# kijek.net
KiCad netlist of a schematic drawn in Altium Designer
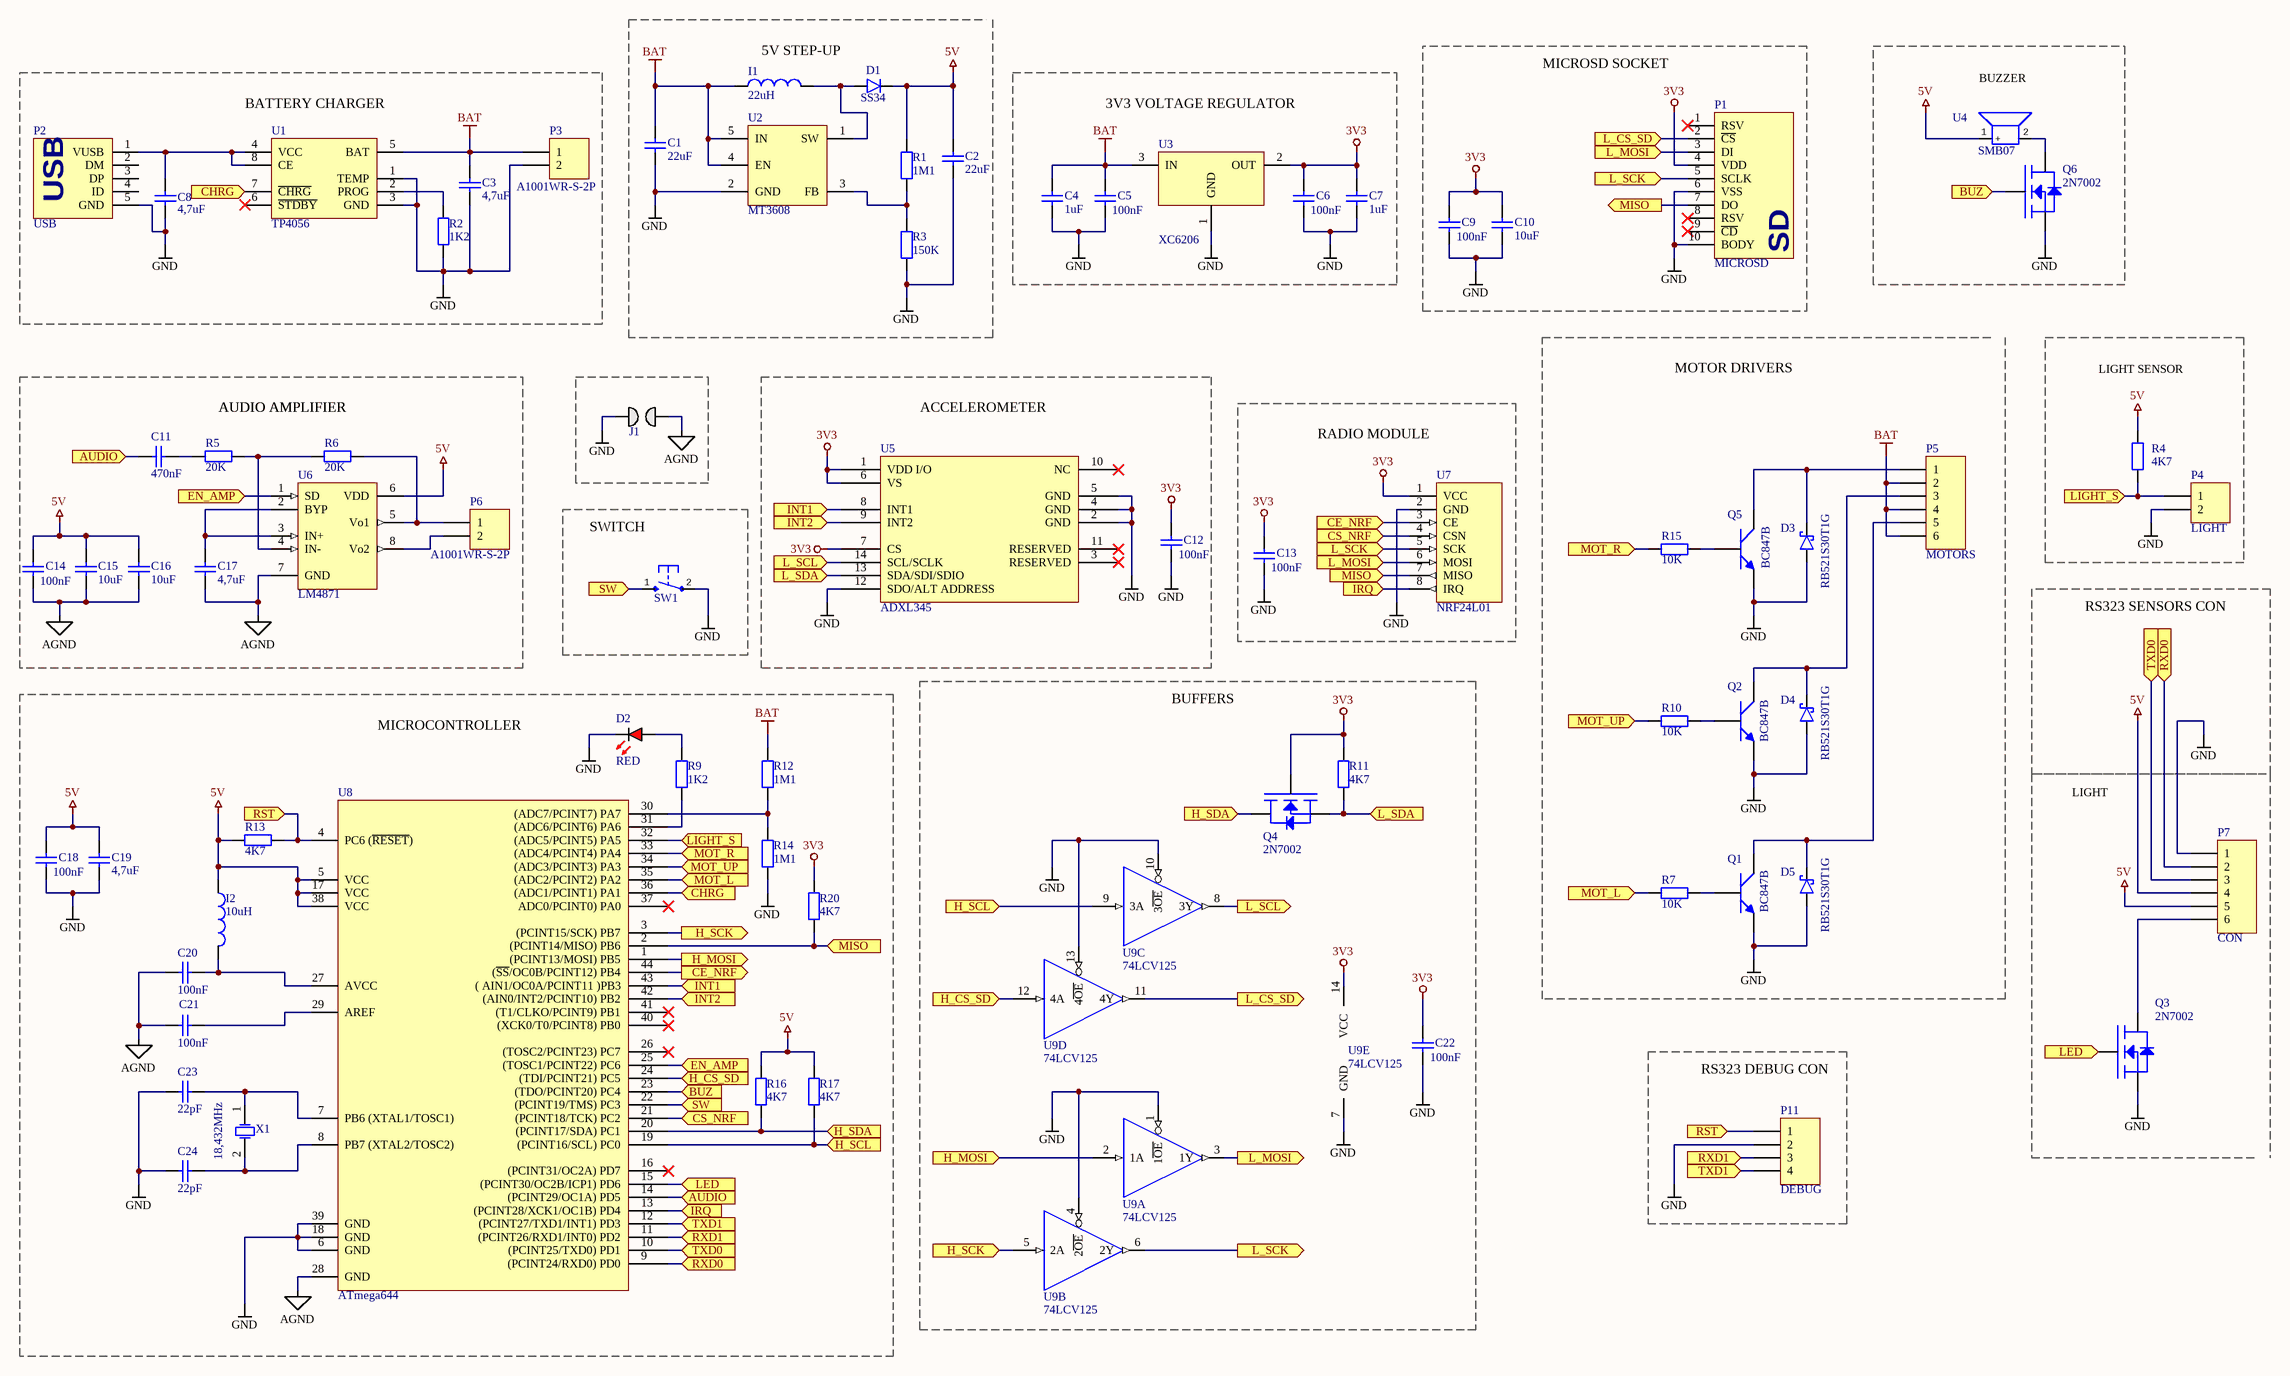
[diagram p0: kijek.SchDoc]

(export (version "E")
  (design (tool "Eeschema 10.0.6"))
  (components
    (comp (ref "C1")
      (value "22uF")
      (footprint "C0603")
      (description "Capacitor")
      (libsource (lib "Library") (part "Cap"))
    )
    (comp (ref "C2")
      (value "22uF")
      (footprint "C0603")
      (description "Capacitor")
      (libsource (lib "Library") (part "Cap"))
    )
    (comp (ref "C3")
      (value "4,7uF")
      (footprint "C0603")
      (description "Capacitor")
      (libsource (lib "Library") (part "Cap"))
    )
    (comp (ref "C4")
      (value "1uF")
      (footprint "C0402")
      (description "Capacitor")
      (libsource (lib "Library") (part "Cap"))
    )
    (comp (ref "C5")
      (value "100nF")
      (footprint "C0402")
      (description "Capacitor")
      (libsource (lib "Library") (part "Cap"))
    )
    (comp (ref "C6")
      (value "100nF")
      (footprint "C0402")
      (description "Capacitor")
      (libsource (lib "Library") (part "Cap"))
    )
    (comp (ref "C7")
      (value "1uF")
      (footprint "C0402")
      (description "Capacitor")
      (libsource (lib "Library") (part "Cap"))
    )
    (comp (ref "C8")
      (value "4,7uF")
      (footprint "C0603")
      (description "Capacitor")
      (libsource (lib "Library") (part "Cap"))
    )
    (comp (ref "C9")
      (value "100nF")
      (footprint "C0402")
      (description "Capacitor")
      (libsource (lib "Library") (part "Cap"))
    )
    (comp (ref "C10")
      (value "10uF")
      (footprint "C0603")
      (description "Capacitor")
      (libsource (lib "Library") (part "Cap"))
    )
    (comp (ref "C11")
      (value "470nF")
      (footprint "C0402")
      (description "Capacitor")
      (libsource (lib "Library") (part "Cap"))
    )
    (comp (ref "C12")
      (value "100nF")
      (footprint "C0402")
      (description "Capacitor")
      (libsource (lib "Library") (part "Cap"))
    )
    (comp (ref "C13")
      (value "100nF")
      (footprint "C0402")
      (description "Capacitor")
      (libsource (lib "Library") (part "Cap"))
    )
    (comp (ref "C14")
      (value "100nF")
      (footprint "C0402")
      (description "Capacitor")
      (libsource (lib "Library") (part "Cap"))
    )
    (comp (ref "C15")
      (value "10uF")
      (footprint "C0603")
      (description "Capacitor")
      (libsource (lib "Library") (part "Cap"))
    )
    (comp (ref "C16")
      (value "10uF")
      (footprint "C0603")
      (description "Capacitor")
      (libsource (lib "Library") (part "Cap"))
    )
    (comp (ref "C17")
      (value "4,7uF")
      (footprint "C0603")
      (description "Capacitor")
      (libsource (lib "Library") (part "Cap"))
    )
    (comp (ref "C18")
      (value "100nF")
      (footprint "C0402")
      (description "Capacitor")
      (libsource (lib "Library") (part "Cap"))
    )
    (comp (ref "C19")
      (value "4,7uF")
      (footprint "C0603")
      (description "Capacitor")
      (libsource (lib "Library") (part "Cap"))
    )
    (comp (ref "C20")
      (value "100nF")
      (footprint "C0402")
      (description "Capacitor")
      (libsource (lib "Library") (part "Cap"))
    )
    (comp (ref "C21")
      (value "100nF")
      (footprint "C0402")
      (description "Capacitor")
      (libsource (lib "Library") (part "Cap"))
    )
    (comp (ref "C22")
      (value "100nF")
      (footprint "C0402")
      (description "Capacitor")
      (libsource (lib "Library") (part "Cap"))
    )
    (comp (ref "C23")
      (value "22pF")
      (footprint "C0402")
      (description "Capacitor")
      (libsource (lib "Library") (part "Cap"))
    )
    (comp (ref "C24")
      (value "22pF")
      (footprint "C0402")
      (description "Capacitor")
      (libsource (lib "Library") (part "Cap"))
    )
    (comp (ref "D1") (value "SS34") (footprint "SMA") (libsource (lib "Library") (part "Diode")))
    (comp (ref "D2")
      (value "RED")
      (footprint "LED0603")
      (description "LED")
      (libsource (lib "Library") (part "LED_RED"))
    )
    (comp (ref "D3")
      (value "RB521S30T1G")
      (footprint "SOD523")
      (libsource (lib "Library") (part "Diode Shottky"))
    )
    (comp (ref "D4")
      (value "RB521S30T1G")
      (footprint "SOD523")
      (libsource (lib "Library") (part "Diode Shottky"))
    )
    (comp (ref "D5")
      (value "RB521S30T1G")
      (footprint "SOD523")
      (libsource (lib "Library") (part "Diode Shottky"))
    )
    (comp (ref "I1") (value "22uH") (footprint "6x6x2.8mm") (libsource (lib "Library") (part "Inductor")))
    (comp (ref "I2") (value "10uH") (footprint "I0603") (libsource (lib "Library") (part "Inductor")))
    (comp (ref "J1")
      (value "SOLDER_JUMPER")
      (footprint "SOLDER_JUMPER")
      (description "Header, 2-Pin")
      (libsource (lib "Connectors") (part "SOLDER_JUMPER"))
    )
    (comp (ref "P1") (value "MICROSD") (footprint "MICROSD") (libsource (lib "Connectors") (part "MICROSD")))
    (comp (ref "P2") (value "USB") (footprint "MICRO_USB_2") (libsource (lib "Connectors") (part "USB_2.0")))
    (comp (ref "P3")
      (value "A1001WR-S-2P")
      (footprint "A1001WR-S-2P")
      (description "Header, 2-Pin")
      (libsource (lib "Connectors") (part "A1001WR-S-2P"))
    )
    (comp (ref "P4")
      (value "LIGHT")
      (footprint "A1001WR-S-2P")
      (description "Header, 2-Pin")
      (libsource (lib "Connectors") (part "A1001WR-S-2P"))
    )
    (comp (ref "P5")
      (value "MOTORS")
      (footprint "A1001WR-S-6P")
      (description "Header, 6-Pin")
      (libsource (lib "Connectors") (part "Header 6"))
    )
    (comp (ref "P6")
      (value "A1001WR-S-2P")
      (footprint "A1001WR-S-2P")
      (description "Header, 2-Pin")
      (libsource (lib "Connectors") (part "A1001WR-S-2P"))
    )
    (comp (ref "P7")
      (value "CON")
      (footprint "MX-502352-0600")
      (description "Header, 6-Pin")
      (libsource (lib "Connectors") (part "Header 6"))
    )
    (comp (ref "P11")
      (value "DEBUG")
      (footprint "PAD_4-1")
      (description "Header, 4-Pin")
      (libsource (lib "Connectors") (part "Header 4"))
    )
    (comp (ref "Q1")
      (value "BC847B")
      (footprint "SOT23")
      (description "NPN")
      (libsource (lib "Library") (part "BC847C(BEC)"))
    )
    (comp (ref "Q2")
      (value "BC847B")
      (footprint "SOT23")
      (description "NPN")
      (libsource (lib "Library") (part "BC847C(BEC)"))
    )
    (comp (ref "Q3")
      (value "2N7002")
      (footprint "SOT23")
      (description "N-MOSFET")
      (libsource (lib "Library") (part "2N7002(GSD)"))
    )
    (comp (ref "Q4")
      (value "2N7002")
      (footprint "SOT23")
      (description "N-MOSFET")
      (libsource (lib "Library") (part "2N7002(GSD)"))
    )
    (comp (ref "Q5")
      (value "BC847B")
      (footprint "SOT23")
      (description "NPN")
      (libsource (lib "Library") (part "BC847C(BEC)"))
    )
    (comp (ref "Q6")
      (value "2N7002")
      (footprint "SOT23")
      (description "N-MOSFET")
      (libsource (lib "Library") (part "2N7002(GSD)"))
    )
    (comp (ref "R1")
      (value "1M1")
      (footprint "R0402")
      (description "Resistor")
      (libsource (lib "Library") (part "Res"))
    )
    (comp (ref "R2")
      (value "1K2")
      (footprint "R0402")
      (description "Resistor")
      (libsource (lib "") (part "Res_1"))
    )
    (comp (ref "R3")
      (value "150K")
      (footprint "R0402")
      (description "Resistor")
      (libsource (lib "Library") (part "Res"))
    )
    (comp (ref "R4")
      (value "4K7")
      (footprint "R0402")
      (description "Resistor")
      (libsource (lib "altium-import") (part "root_1_Res_"))
    )
    (comp (ref "R5")
      (value "20K")
      (footprint "R0402")
      (description "Resistor")
      (libsource (lib "") (part "Res_2"))
    )
    (comp (ref "R6")
      (value "20K")
      (footprint "R0402")
      (description "Resistor")
      (libsource (lib "") (part "Res_2"))
    )
    (comp (ref "R7")
      (value "10K")
      (footprint "R0402")
      (description "Resistor")
      (libsource (lib "") (part "Res_3"))
    )
    (comp (ref "R9")
      (value "1K2")
      (footprint "R0402")
      (description "Resistor")
      (libsource (lib "Library") (part "Res"))
    )
    (comp (ref "R10")
      (value "10K")
      (footprint "R0402")
      (description "Resistor")
      (libsource (lib "") (part "Res_3"))
    )
    (comp (ref "R11")
      (value "4K7")
      (footprint "R0402")
      (description "Resistor")
      (libsource (lib "Library") (part "Res"))
    )
    (comp (ref "R12")
      (value "1M1")
      (footprint "R0402")
      (description "Resistor")
      (libsource (lib "") (part "Res_1"))
    )
    (comp (ref "R13")
      (value "4K7")
      (footprint "R0402")
      (description "Resistor")
      (libsource (lib "") (part "Res_2"))
    )
    (comp (ref "R14")
      (value "1M1")
      (footprint "R0402")
      (description "Resistor")
      (libsource (lib "Library") (part "Res"))
    )
    (comp (ref "R15")
      (value "10K")
      (footprint "R0402")
      (description "Resistor")
      (libsource (lib "") (part "Res_3"))
    )
    (comp (ref "R16")
      (value "4K7")
      (footprint "R0402")
      (description "Resistor")
      (libsource (lib "Library") (part "Res"))
    )
    (comp (ref "R17")
      (value "4K7")
      (footprint "R0402")
      (description "Resistor")
      (libsource (lib "Library") (part "Res"))
    )
    (comp (ref "R20")
      (value "4K7")
      (footprint "R0402")
      (description "Resistor")
      (libsource (lib "Library") (part "Res"))
    )
    (comp (ref "SW1")
      (value "SW_3x6x3.5mm")
      (footprint "3x6x3.5mm")
      (libsource (lib "Library") (part "SW_3x6x3.5mm"))
    )
    (comp (ref "U1") (value "TP4056") (footprint "SO-8") (libsource (lib "IC") (part "TP4056")))
    (comp (ref "U2") (value "MT3608") (footprint "SOT-23-6") (libsource (lib "IC") (part "MT3608")))
    (comp (ref "U3") (value "XC6206") (footprint "SOT23") (libsource (lib "IC") (part "XC6206")))
    (comp (ref "U4") (value "SMB07") (footprint "SMB07") (libsource (lib "Library") (part "BUZ_SMB07")))
    (comp (ref "U5") (value "ADXL345") (footprint "LGA_CC-14") (libsource (lib "IC") (part "ADXL345")))
    (comp (ref "U6") (value "LM4871") (footprint "SO-8") (libsource (lib "IC") (part "LM4871")))
    (comp (ref "U7") (value "NRF24L01") (footprint "NRF24L01") (libsource (lib "Library") (part "NRF24L01")))
    (comp (ref "U8")
      (value "ATmega644")
      (footprint "TQFP-44A")
      (description "TQFP - 44pin / MLF - 44pin")
      (libsource (lib "IC") (part "ATmega644"))
    )
    (comp (ref "U9")
      (value "74LCV125")
      (footprint "TSSOP-14")
      (description "BUFFERS (3-STATE)")
      (libsource (lib "IC") (part "74LCV125"))
    )
    (comp (ref "X1") (value "18,432MHz") (footprint "CFPX-104") (libsource (lib "Library") (part "Crystal")))
  )
  (nets
    (net (code "1") (name "/AUDIO") (class "Default")
      (node (ref "C11") (pin "1") (pinfunction "1_1") (pintype "passive"))
      (node (ref "U8") (pin "14") (pinfunction "(PCINT29/OC1A)_PD5_14") (pintype "passive"))
    )
    (net (code "2") (name "/BUZ") (class "Default")
      (node (ref "Q6") (pin "1") (pinfunction "G_1") (pintype "passive"))
      (node (ref "U8") (pin "23") (pinfunction "(TDO/PCINT20)_PC4_23") (pintype "passive"))
    )
    (net (code "3") (name "/CE_NRF") (class "Default")
      (node (ref "U7") (pin "3") (pinfunction "CE_3") (pintype "input"))
      (node (ref "U8") (pin "44") (pinfunction "(~{SS}/OC0B/PCINT12)_PB4_44") (pintype "passive"))
    )
    (net (code "4") (name "/CHRG") (class "Default")
      (node (ref "U1") (pin "7") (pinfunction "~{CHRG}_7") (pintype "power_in"))
      (node (ref "U8") (pin "36") (pinfunction "(ADC1/PCINT1)_PA1_36") (pintype "passive"))
    )
    (net (code "5") (name "/CS_NRF") (class "Default")
      (node (ref "U7") (pin "4") (pinfunction "CSN_4") (pintype "input"))
      (node (ref "U8") (pin "21") (pinfunction "(PCINT18/TCK)_PC2_21") (pintype "passive"))
    )
    (net (code "6") (name "/EN_AMP") (class "Default")
      (node (ref "U6") (pin "1") (pinfunction "SD_1") (pintype "input"))
      (node (ref "U8") (pin "25") (pinfunction "(TOSC1/PCINT22)_PC6_25") (pintype "passive"))
    )
    (net (code "7") (name "/H_CS_SD") (class "Default")
      (node (ref "U8") (pin "24") (pinfunction "(TDI/PCINT21)_PC5_24") (pintype "passive"))
      (node (ref "U9") (pin "12") (pinfunction "4A_12") (pintype "input"))
    )
    (net (code "8") (name "/H_MOSI") (class "Default")
      (node (ref "U8") (pin "1") (pinfunction "(PCINT13/MOSI)_PB5_1") (pintype "passive"))
      (node (ref "U9") (pin "2") (pinfunction "1A_2") (pintype "input"))
    )
    (net (code "9") (name "/H_SCK") (class "Default")
      (node (ref "U8") (pin "3") (pinfunction "(PCINT15/SCK)_PB7_3") (pintype "passive"))
      (node (ref "U9") (pin "5") (pinfunction "2A_5") (pintype "input"))
    )
    (net (code "10") (name "/H_SCL") (class "Default")
      (node (ref "R17") (pin "2") (pinfunction "2_2") (pintype "passive"))
      (node (ref "U8") (pin "19") (pinfunction "(PCINT16/SCL)_PC0_19") (pintype "passive"))
      (node (ref "U9") (pin "9") (pinfunction "3A_9") (pintype "input"))
    )
    (net (code "11") (name "/H_SDA") (class "Default")
      (node (ref "Q4") (pin "3") (pinfunction "D_3") (pintype "passive"))
      (node (ref "R16") (pin "2") (pinfunction "2_2") (pintype "passive"))
      (node (ref "U8") (pin "20") (pinfunction "(PCINT17/SDA)_PC1_20") (pintype "passive"))
    )
    (net (code "12") (name "/INT1") (class "Default")
      (node (ref "U5") (pin "8") (pinfunction "INT1_8") (pintype "passive"))
      (node (ref "U8") (pin "43") (pinfunction "(_AIN1/OC0A/PCINT11_)PB3_43") (pintype "passive"))
    )
    (net (code "13") (name "/INT2") (class "Default")
      (node (ref "U5") (pin "9") (pinfunction "INT2_9") (pintype "passive"))
      (node (ref "U8") (pin "42") (pinfunction "(AIN0/INT2/PCINT10)_PB2_42") (pintype "passive"))
    )
    (net (code "14") (name "/IRQ") (class "Default")
      (node (ref "U7") (pin "8") (pinfunction "IRQ_8") (pintype "output"))
      (node (ref "U8") (pin "13") (pinfunction "(PCINT28/XCK1/OC1B)_PD4_13") (pintype "passive"))
    )
    (net (code "15") (name "/LED") (class "Default")
      (node (ref "Q3") (pin "1") (pinfunction "G_1") (pintype "passive"))
      (node (ref "U8") (pin "15") (pinfunction "(PCINT30/OC2B/ICP1)_PD6_15") (pintype "passive"))
    )
    (net (code "16") (name "/LIGHT_S") (class "Default")
      (node (ref "P4") (pin "1") (pinfunction "1_1") (pintype "passive"))
      (node (ref "R4") (pin "1") (pinfunction "1_1") (pintype "passive"))
      (node (ref "U8") (pin "32") (pinfunction "(ADC5/PCINT5)_PA5_32") (pintype "passive"))
    )
    (net (code "17") (name "/L_CS_SD") (class "Default")
      (node (ref "P1") (pin "2") (pinfunction "~{CS}_2") (pintype "passive"))
      (node (ref "U9") (pin "11") (pinfunction "4Y_11") (pintype "output"))
    )
    (net (code "18") (name "/L_MOSI") (class "Default")
      (node (ref "P1") (pin "3") (pinfunction "DI_3") (pintype "passive"))
      (node (ref "U7") (pin "6") (pinfunction "MOSI_6") (pintype "input"))
      (node (ref "U9") (pin "3") (pinfunction "1Y_3") (pintype "output"))
    )
    (net (code "19") (name "/L_SCK") (class "Default")
      (node (ref "P1") (pin "5") (pinfunction "SCLK_5") (pintype "passive"))
      (node (ref "U7") (pin "5") (pinfunction "SCK_5") (pintype "input"))
      (node (ref "U9") (pin "6") (pinfunction "2Y_6") (pintype "output"))
    )
    (net (code "20") (name "/L_SCL") (class "Default")
      (node (ref "U5") (pin "14") (pinfunction "SCL/SCLK_14") (pintype "passive"))
      (node (ref "U9") (pin "8") (pinfunction "3Y_8") (pintype "output"))
    )
    (net (code "21") (name "/L_SDA") (class "Default")
      (node (ref "Q4") (pin "2") (pinfunction "S_2") (pintype "passive"))
      (node (ref "R11") (pin "2") (pinfunction "2_2") (pintype "passive"))
      (node (ref "U5") (pin "13") (pinfunction "SDA/SDI/SDIO_13") (pintype "passive"))
    )
    (net (code "22") (name "/MISO") (class "Default")
      (node (ref "P1") (pin "7") (pinfunction "DO_7") (pintype "passive"))
      (node (ref "R20") (pin "2") (pinfunction "2_2") (pintype "passive"))
      (node (ref "U7") (pin "7") (pinfunction "MISO_7") (pintype "output"))
      (node (ref "U8") (pin "2") (pinfunction "(PCINT14/MISO)_PB6_2") (pintype "passive"))
    )
    (net (code "23") (name "/MOT_L") (class "Default")
      (node (ref "R7") (pin "2") (pinfunction "2_2") (pintype "passive"))
      (node (ref "U8") (pin "35") (pinfunction "(ADC2/PCINT2)_PA2_35") (pintype "passive"))
    )
    (net (code "24") (name "/MOT_R") (class "Default")
      (node (ref "R15") (pin "2") (pinfunction "2_2") (pintype "passive"))
      (node (ref "U8") (pin "33") (pinfunction "(ADC4/PCINT4)_PA4_33") (pintype "passive"))
    )
    (net (code "25") (name "/MOT_UP") (class "Default")
      (node (ref "R10") (pin "2") (pinfunction "2_2") (pintype "passive"))
      (node (ref "U8") (pin "34") (pinfunction "(ADC3/PCINT3)_PA3_34") (pintype "passive"))
    )
    (net (code "26") (name "/RST") (class "Default")
      (node (ref "P11") (pin "1") (pinfunction "1_1") (pintype "passive"))
      (node (ref "R13") (pin "2") (pinfunction "2_2") (pintype "passive"))
      (node (ref "U8") (pin "4") (pinfunction "PC6_(~{RESET})_4") (pintype "passive"))
    )
    (net (code "27") (name "/RXD0") (class "Default")
      (node (ref "P7") (pin "2") (pinfunction "2_2") (pintype "passive"))
      (node (ref "U8") (pin "9") (pinfunction "(PCINT24/RXD0)_PD0_9") (pintype "passive"))
    )
    (net (code "28") (name "/RXD1") (class "Default")
      (node (ref "P11") (pin "3") (pinfunction "3_3") (pintype "passive"))
      (node (ref "U8") (pin "11") (pinfunction "(PCINT26/RXD1/INT0)_PD2_11") (pintype "passive"))
    )
    (net (code "29") (name "/SW") (class "Default")
      (node (ref "SW1") (pin "1") (pinfunction "S_1") (pintype "passive"))
      (node (ref "U8") (pin "22") (pinfunction "(PCINT19/TMS)_PC3_22") (pintype "passive"))
    )
    (net (code "30") (name "/TXD0") (class "Default")
      (node (ref "P7") (pin "3") (pinfunction "3_3") (pintype "passive"))
      (node (ref "U8") (pin "10") (pinfunction "(PCINT25/TXD0)_PD1_10") (pintype "passive"))
    )
    (net (code "31") (name "/TXD1") (class "Default")
      (node (ref "P11") (pin "4") (pinfunction "4_4") (pintype "passive"))
      (node (ref "U8") (pin "12") (pinfunction "(PCINT27/TXD1/INT1)_PD3_12") (pintype "passive"))
    )
    (net (code "32") (name "3V3") (class "Default")
      (node (ref "C10") (pin "1") (pinfunction "1_1") (pintype "passive"))
      (node (ref "C12") (pin "1") (pinfunction "1_1") (pintype "passive"))
      (node (ref "C13") (pin "1") (pinfunction "1_1") (pintype "passive"))
      (node (ref "C22") (pin "1") (pinfunction "1_1") (pintype "passive"))
      (node (ref "C6") (pin "1") (pinfunction "1_1") (pintype "passive"))
      (node (ref "C7") (pin "1") (pinfunction "1_1") (pintype "passive"))
      (node (ref "C9") (pin "1") (pinfunction "1_1") (pintype "passive"))
      (node (ref "P1") (pin "4") (pinfunction "VDD_4") (pintype "power_in"))
      (node (ref "Q4") (pin "1") (pinfunction "G_1") (pintype "passive"))
      (node (ref "R11") (pin "1") (pinfunction "1_1") (pintype "passive"))
      (node (ref "R20") (pin "1") (pinfunction "1_1") (pintype "passive"))
      (node (ref "U3") (pin "2") (pinfunction "OUT_2") (pintype "power_in"))
      (node (ref "U5") (pin "1") (pinfunction "VDD_I/O_1") (pintype "passive"))
      (node (ref "U5") (pin "6") (pinfunction "VS_6") (pintype "passive"))
      (node (ref "U5") (pin "7") (pinfunction "CS_7") (pintype "passive"))
      (node (ref "U7") (pin "1") (pinfunction "VCC_1") (pintype "power_in"))
      (node (ref "U9") (pin "14") (pinfunction "VCC_14") (pintype "power_in"))
    )
    (net (code "33") (name "5V") (class "Default")
      (node (ref "C14") (pin "1") (pinfunction "1_1") (pintype "passive"))
      (node (ref "C15") (pin "1") (pinfunction "1_1") (pintype "passive"))
      (node (ref "C16") (pin "1") (pinfunction "1_1") (pintype "passive"))
      (node (ref "C18") (pin "1") (pinfunction "1_1") (pintype "passive"))
      (node (ref "C19") (pin "1") (pinfunction "1_1") (pintype "passive"))
      (node (ref "C2") (pin "1") (pinfunction "1_1") (pintype "passive"))
      (node (ref "D1") (pin "1") (pinfunction "1_1") (pintype "power_in"))
      (node (ref "I2") (pin "1") (pinfunction "1_1") (pintype "passive"))
      (node (ref "P7") (pin "4") (pinfunction "4_4") (pintype "passive"))
      (node (ref "P7") (pin "5") (pinfunction "5_5") (pintype "passive"))
      (node (ref "R1") (pin "1") (pinfunction "1_1") (pintype "passive"))
      (node (ref "R13") (pin "1") (pinfunction "1_1") (pintype "passive"))
      (node (ref "R16") (pin "1") (pinfunction "1_1") (pintype "passive"))
      (node (ref "R17") (pin "1") (pinfunction "1_1") (pintype "passive"))
      (node (ref "R4") (pin "2") (pinfunction "2_2") (pintype "passive"))
      (node (ref "U4") (pin "1") (pinfunction "+_1") (pintype "passive"))
      (node (ref "U6") (pin "6") (pinfunction "VDD_6") (pintype "power_in"))
      (node (ref "U8") (pin "17") (pinfunction "VCC_17") (pintype "power_in"))
      (node (ref "U8") (pin "38") (pinfunction "VCC_38") (pintype "power_in"))
      (node (ref "U8") (pin "5") (pinfunction "VCC_5") (pintype "power_in"))
    )
    (net (code "34") (name "AGND") (class "Default")
      (node (ref "C14") (pin "2") (pinfunction "2_2") (pintype "passive"))
      (node (ref "C15") (pin "2") (pinfunction "2_2") (pintype "passive"))
      (node (ref "C16") (pin "2") (pinfunction "2_2") (pintype "passive"))
      (node (ref "C17") (pin "2") (pinfunction "2_2") (pintype "passive"))
      (node (ref "C20") (pin "1") (pinfunction "1_1") (pintype "passive"))
      (node (ref "C21") (pin "2") (pinfunction "2_2") (pintype "passive"))
      (node (ref "J1") (pin "2") (pinfunction "2_2") (pintype "passive"))
      (node (ref "U6") (pin "7") (pinfunction "GND_7") (pintype "power_in"))
      (node (ref "U8") (pin "28") (pinfunction "GND_28") (pintype "power_in"))
    )
    (net (code "35") (name "BAT") (class "Default")
      (node (ref "C1") (pin "1") (pinfunction "1_1") (pintype "passive"))
      (node (ref "C3") (pin "1") (pinfunction "1_1") (pintype "passive"))
      (node (ref "C4") (pin "1") (pinfunction "1_1") (pintype "passive"))
      (node (ref "C5") (pin "1") (pinfunction "1_1") (pintype "passive"))
      (node (ref "I1") (pin "1") (pinfunction "1_1") (pintype "passive"))
      (node (ref "P3") (pin "1") (pinfunction "1_1") (pintype "passive"))
      (node (ref "P5") (pin "2") (pinfunction "2_2") (pintype "passive"))
      (node (ref "P5") (pin "4") (pinfunction "4_4") (pintype "passive"))
      (node (ref "P5") (pin "6") (pinfunction "6_6") (pintype "passive"))
      (node (ref "R12") (pin "2") (pinfunction "2_2") (pintype "passive"))
      (node (ref "U1") (pin "5") (pinfunction "BAT_5") (pintype "power_in"))
      (node (ref "U2") (pin "4") (pinfunction "EN_4") (pintype "passive"))
      (node (ref "U2") (pin "5") (pinfunction "IN_5") (pintype "passive"))
      (node (ref "U3") (pin "3") (pinfunction "IN_3") (pintype "power_in"))
    )
    (net (code "36") (name "GND") (class "Default")
      (node (ref "C1") (pin "2") (pinfunction "2_2") (pintype "passive"))
      (node (ref "C10") (pin "2") (pinfunction "2_2") (pintype "passive"))
      (node (ref "C12") (pin "2") (pinfunction "2_2") (pintype "passive"))
      (node (ref "C13") (pin "2") (pinfunction "2_2") (pintype "passive"))
      (node (ref "C18") (pin "2") (pinfunction "2_2") (pintype "passive"))
      (node (ref "C19") (pin "2") (pinfunction "2_2") (pintype "passive"))
      (node (ref "C2") (pin "2") (pinfunction "2_2") (pintype "passive"))
      (node (ref "C22") (pin "2") (pinfunction "2_2") (pintype "passive"))
      (node (ref "C23") (pin "1") (pinfunction "1_1") (pintype "passive"))
      (node (ref "C24") (pin "2") (pinfunction "2_2") (pintype "passive"))
      (node (ref "C3") (pin "2") (pinfunction "2_2") (pintype "passive"))
      (node (ref "C4") (pin "2") (pinfunction "2_2") (pintype "passive"))
      (node (ref "C5") (pin "2") (pinfunction "2_2") (pintype "passive"))
      (node (ref "C6") (pin "2") (pinfunction "2_2") (pintype "passive"))
      (node (ref "C7") (pin "2") (pinfunction "2_2") (pintype "passive"))
      (node (ref "C8") (pin "2") (pinfunction "2_2") (pintype "passive"))
      (node (ref "C9") (pin "2") (pinfunction "2_2") (pintype "passive"))
      (node (ref "D2") (pin "1") (pinfunction "1_1") (pintype "passive"))
      (node (ref "D3") (pin "2") (pinfunction "2_2") (pintype "power_in"))
      (node (ref "D4") (pin "2") (pinfunction "2_2") (pintype "power_in"))
      (node (ref "D5") (pin "2") (pinfunction "2_2") (pintype "power_in"))
      (node (ref "J1") (pin "1") (pinfunction "1_1") (pintype "passive"))
      (node (ref "P1") (pin "10") (pinfunction "BODY_10") (pintype "passive"))
      (node (ref "P1") (pin "6") (pinfunction "VSS_6") (pintype "passive"))
      (node (ref "P11") (pin "2") (pinfunction "2_2") (pintype "passive"))
      (node (ref "P2") (pin "5") (pinfunction "GND_5") (pintype "power_in"))
      (node (ref "P3") (pin "2") (pinfunction "2_2") (pintype "passive"))
      (node (ref "P4") (pin "2") (pinfunction "2_2") (pintype "passive"))
      (node (ref "P7") (pin "1") (pinfunction "1_1") (pintype "passive"))
      (node (ref "Q1") (pin "2") (pinfunction "E_2") (pintype "passive"))
      (node (ref "Q2") (pin "2") (pinfunction "E_2") (pintype "passive"))
      (node (ref "Q3") (pin "2") (pinfunction "S_2") (pintype "passive"))
      (node (ref "Q5") (pin "2") (pinfunction "E_2") (pintype "passive"))
      (node (ref "Q6") (pin "2") (pinfunction "S_2") (pintype "passive"))
      (node (ref "R14") (pin "2") (pinfunction "2_2") (pintype "passive"))
      (node (ref "R2") (pin "1") (pinfunction "1_1") (pintype "passive"))
      (node (ref "R3") (pin "2") (pinfunction "2_2") (pintype "passive"))
      (node (ref "SW1") (pin "2") (pinfunction "P_2") (pintype "passive"))
      (node (ref "U1") (pin "1") (pinfunction "TEMP_1") (pintype "passive"))
      (node (ref "U1") (pin "3") (pinfunction "GND_3") (pintype "power_in"))
      (node (ref "U2") (pin "2") (pinfunction "GND_2") (pintype "passive"))
      (node (ref "U3") (pin "1") (pinfunction "GND_1") (pintype "power_in"))
      (node (ref "U5") (pin "12") (pinfunction "SDO/ALT_ADDRESS_12") (pintype "passive"))
      (node (ref "U5") (pin "2") (pinfunction "GND_2") (pintype "passive"))
      (node (ref "U5") (pin "4") (pinfunction "GND_4") (pintype "passive"))
      (node (ref "U5") (pin "5") (pinfunction "GND_5") (pintype "passive"))
      (node (ref "U7") (pin "2") (pinfunction "GND_2") (pintype "power_in"))
      (node (ref "U8") (pin "18") (pinfunction "GND_18") (pintype "power_in"))
      (node (ref "U8") (pin "39") (pinfunction "GND_39") (pintype "power_in"))
      (node (ref "U8") (pin "6") (pinfunction "GND_6") (pintype "power_in"))
      (node (ref "U9") (pin "1") (pinfunction "1~{OE}_1") (pintype "input"))
      (node (ref "U9") (pin "10") (pinfunction "3~{OE}_10") (pintype "input"))
      (node (ref "U9") (pin "13") (pinfunction "4~{OE}_13") (pintype "input"))
      (node (ref "U9") (pin "4") (pinfunction "2~{OE}_4") (pintype "input"))
      (node (ref "U9") (pin "7") (pinfunction "GND_7") (pintype "power_in"))
    )
    (net (code "37") (name "Net-(C11-Pad2)") (class "Default")
      (node (ref "C11") (pin "2") (pinfunction "2_2") (pintype "passive"))
      (node (ref "R5") (pin "1") (pinfunction "1_1") (pintype "passive"))
    )
    (net (code "38") (name "Net-(D2-Pad2)") (class "Default")
      (node (ref "D2") (pin "2") (pinfunction "2_2") (pintype "passive"))
      (node (ref "R9") (pin "1") (pinfunction "1_1") (pintype "passive"))
    )
    (net (code "39") (name "Net-(P2-VUSB)") (class "Default")
      (node (ref "C8") (pin "1") (pinfunction "1_1") (pintype "passive"))
      (node (ref "P2") (pin "1") (pinfunction "VUSB_1") (pintype "power_in"))
      (node (ref "U1") (pin "4") (pinfunction "VCC_4") (pintype "power_in"))
      (node (ref "U1") (pin "8") (pinfunction "CE_8") (pintype "power_in"))
    )
    (net (code "40") (name "Net-(Q1-B)") (class "Default")
      (node (ref "Q1") (pin "1") (pinfunction "B_1") (pintype "passive"))
      (node (ref "R7") (pin "1") (pinfunction "1_1") (pintype "passive"))
    )
    (net (code "41") (name "Net-(Q1-C)") (class "Default")
      (node (ref "D5") (pin "1") (pinfunction "1_1") (pintype "power_in"))
      (node (ref "P5") (pin "5") (pinfunction "5_5") (pintype "passive"))
      (node (ref "Q1") (pin "3") (pinfunction "C_3") (pintype "passive"))
    )
    (net (code "42") (name "Net-(Q2-B)") (class "Default")
      (node (ref "Q2") (pin "1") (pinfunction "B_1") (pintype "passive"))
      (node (ref "R10") (pin "1") (pinfunction "1_1") (pintype "passive"))
    )
    (net (code "43") (name "Net-(Q2-C)") (class "Default")
      (node (ref "D4") (pin "1") (pinfunction "1_1") (pintype "power_in"))
      (node (ref "P5") (pin "3") (pinfunction "3_3") (pintype "passive"))
      (node (ref "Q2") (pin "3") (pinfunction "C_3") (pintype "passive"))
    )
    (net (code "44") (name "Net-(Q3-D)") (class "Default")
      (node (ref "P7") (pin "6") (pinfunction "6_6") (pintype "passive"))
      (node (ref "Q3") (pin "3") (pinfunction "D_3") (pintype "passive"))
    )
    (net (code "45") (name "Net-(Q5-B)") (class "Default")
      (node (ref "Q5") (pin "1") (pinfunction "B_1") (pintype "passive"))
      (node (ref "R15") (pin "1") (pinfunction "1_1") (pintype "passive"))
    )
    (net (code "46") (name "Net-(Q5-C)") (class "Default")
      (node (ref "D3") (pin "1") (pinfunction "1_1") (pintype "power_in"))
      (node (ref "P5") (pin "1") (pinfunction "1_1") (pintype "passive"))
      (node (ref "Q5") (pin "3") (pinfunction "C_3") (pintype "passive"))
    )
    (net (code "47") (name "Net-(Q6-D)") (class "Default")
      (node (ref "Q6") (pin "3") (pinfunction "D_3") (pintype "passive"))
      (node (ref "U4") (pin "2") (pinfunction "2_2") (pintype "passive"))
    )
    (net (code "48") (name "Net-(U1-PROG)") (class "Default")
      (node (ref "R2") (pin "2") (pinfunction "2_2") (pintype "passive"))
      (node (ref "U1") (pin "2") (pinfunction "PROG_2") (pintype "passive"))
    )
    (net (code "49") (name "Net-(U2-FB)") (class "Default")
      (node (ref "R1") (pin "2") (pinfunction "2_2") (pintype "passive"))
      (node (ref "R3") (pin "1") (pinfunction "1_1") (pintype "passive"))
      (node (ref "U2") (pin "3") (pinfunction "FB_3") (pintype "passive"))
    )
    (net (code "50") (name "Net-(U2-SW)") (class "Default")
      (node (ref "D1") (pin "2") (pinfunction "2_2") (pintype "power_in"))
      (node (ref "I1") (pin "2") (pinfunction "2_2") (pintype "passive"))
      (node (ref "U2") (pin "1") (pinfunction "SW_1") (pintype "passive"))
    )
    (net (code "51") (name "Net-(U6-BYP)") (class "Default")
      (node (ref "C17") (pin "1") (pinfunction "1_1") (pintype "passive"))
      (node (ref "U6") (pin "2") (pinfunction "BYP_2") (pintype "passive"))
      (node (ref "U6") (pin "3") (pinfunction "IN+_3") (pintype "input"))
    )
    (net (code "52") (name "Net-(U6-IN-)") (class "Default")
      (node (ref "R5") (pin "2") (pinfunction "2_2") (pintype "passive"))
      (node (ref "R6") (pin "1") (pinfunction "1_1") (pintype "passive"))
      (node (ref "U6") (pin "4") (pinfunction "IN-_4") (pintype "input"))
    )
    (net (code "53") (name "Net-(U6-Vo1)") (class "Default")
      (node (ref "P6") (pin "1") (pinfunction "1_1") (pintype "passive"))
      (node (ref "R6") (pin "2") (pinfunction "2_2") (pintype "passive"))
      (node (ref "U6") (pin "5") (pinfunction "Vo1_5") (pintype "output"))
    )
    (net (code "54") (name "Net-(U6-Vo2)") (class "Default")
      (node (ref "P6") (pin "2") (pinfunction "2_2") (pintype "passive"))
      (node (ref "U6") (pin "8") (pinfunction "Vo2_8") (pintype "output"))
    )
    (net (code "55") (name "Net-(U8-(ADC6{slash}PCINT6)_PA6)") (class "Default")
      (node (ref "R9") (pin "2") (pinfunction "2_2") (pintype "passive"))
      (node (ref "U8") (pin "31") (pinfunction "(ADC6/PCINT6)_PA6_31") (pintype "passive"))
    )
    (net (code "56") (name "Net-(U8-(ADC7{slash}PCINT7)_PA7)") (class "Default")
      (node (ref "R12") (pin "1") (pinfunction "1_1") (pintype "passive"))
      (node (ref "R14") (pin "1") (pinfunction "1_1") (pintype "passive"))
      (node (ref "U8") (pin "30") (pinfunction "(ADC7/PCINT7)_PA7_30") (pintype "passive"))
    )
    (net (code "57") (name "Net-(U8-AREF)") (class "Default")
      (node (ref "C21") (pin "1") (pinfunction "1_1") (pintype "passive"))
      (node (ref "U8") (pin "29") (pinfunction "AREF_29") (pintype "passive"))
    )
    (net (code "58") (name "Net-(U8-AVCC)") (class "Default")
      (node (ref "C20") (pin "2") (pinfunction "2_2") (pintype "passive"))
      (node (ref "I2") (pin "2") (pinfunction "2_2") (pintype "passive"))
      (node (ref "U8") (pin "27") (pinfunction "AVCC_27") (pintype "power_in"))
    )
    (net (code "59") (name "Net-(U8-PB6_(XTAL1{slash}TOSC1))") (class "Default")
      (node (ref "C23") (pin "2") (pinfunction "2_2") (pintype "passive"))
      (node (ref "U8") (pin "7") (pinfunction "PB6_(XTAL1/TOSC1)_7") (pintype "passive"))
      (node (ref "X1") (pin "1") (pinfunction "OSC1_1") (pintype "passive"))
    )
    (net (code "60") (name "Net-(U8-PB7_(XTAL2{slash}TOSC2))") (class "Default")
      (node (ref "C24") (pin "1") (pinfunction "1_1") (pintype "passive"))
      (node (ref "U8") (pin "8") (pinfunction "PB7_(XTAL2/TOSC2)_8") (pintype "passive"))
      (node (ref "X1") (pin "2") (pinfunction "OSC2_2") (pintype "passive"))
    )
    (net (code "61") (name "unconnected-(P1-RSV-Pad1)") (class "Default")
      (node (ref "P1") (pin "1") (pinfunction "RSV_1") (pintype "power_in+no_connect"))
    )
    (net (code "62") (name "unconnected-(P1-RSV-Pad8)") (class "Default")
      (node (ref "P1") (pin "8") (pinfunction "RSV_8") (pintype "passive+no_connect"))
    )
    (net (code "63") (name "unconnected-(P1-~{CD}-Pad9)") (class "Default")
      (node (ref "P1") (pin "9") (pinfunction "~{CD}_9") (pintype "passive+no_connect"))
    )
    (net (code "64") (name "unconnected-(P2-DM-Pad2)") (class "Default")
      (node (ref "P2") (pin "2") (pinfunction "DM_2") (pintype "passive"))
    )
    (net (code "65") (name "unconnected-(P2-DP-Pad3)") (class "Default")
      (node (ref "P2") (pin "3") (pinfunction "DP_3") (pintype "passive"))
    )
    (net (code "66") (name "unconnected-(P2-ID-Pad4)") (class "Default")
      (node (ref "P2") (pin "4") (pinfunction "ID_4") (pintype "power_in"))
    )
    (net (code "67") (name "unconnected-(U1-~{STDBY}-Pad6)") (class "Default")
      (node (ref "U1") (pin "6") (pinfunction "~{STDBY}_6") (pintype "power_in+no_connect"))
    )
    (net (code "68") (name "unconnected-(U5-NC-Pad10)") (class "Default")
      (node (ref "U5") (pin "10") (pinfunction "NC_10") (pintype "passive+no_connect"))
    )
    (net (code "69") (name "unconnected-(U5-RESERVED-Pad3)") (class "Default")
      (node (ref "U5") (pin "3") (pinfunction "RESERVED_3") (pintype "passive+no_connect"))
    )
    (net (code "70") (name "unconnected-(U5-RESERVED-Pad11)") (class "Default")
      (node (ref "U5") (pin "11") (pinfunction "RESERVED_11") (pintype "passive+no_connect"))
    )
    (net (code "71") (name "unconnected-(U8-(PCINT31{slash}OC2A)_PD7-Pad16)") (class "Default")
      (node (ref "U8") (pin "16") (pinfunction "(PCINT31/OC2A)_PD7_16") (pintype "passive+no_connect"))
    )
    (net (code "72") (name "unconnected-(U8-(T1{slash}CLKO{slash}PCINT9)_PB1-Pad41)") (class "Default")
      (node (ref "U8") (pin "41") (pinfunction "(T1/CLKO/PCINT9)_PB1_41") (pintype "passive+no_connect"))
    )
    (net (code "73") (name "unconnected-(U8-(TOSC2{slash}PCINT23)_PC7-Pad26)") (class "Default")
      (node (ref "U8") (pin "26") (pinfunction "(TOSC2/PCINT23)_PC7_26") (pintype "passive+no_connect"))
    )
    (net (code "74") (name "unconnected-(U8-(XCK0{slash}T0{slash}PCINT8)_PB0-Pad40)") (class "Default")
      (node (ref "U8") (pin "40") (pinfunction "(XCK0/T0/PCINT8)_PB0_40") (pintype "passive+no_connect"))
    )
    (net (code "75") (name "unconnected-(U8-ADC0{slash}PCINT0)_PA0-Pad37)") (class "Default")
      (node (ref "U8") (pin "37") (pinfunction "ADC0/PCINT0)_PA0_37") (pintype "passive+no_connect"))
    )
  )
)
